# dcdr_3_2.net
KiCad netlist of a schematic drawn in EAGLE
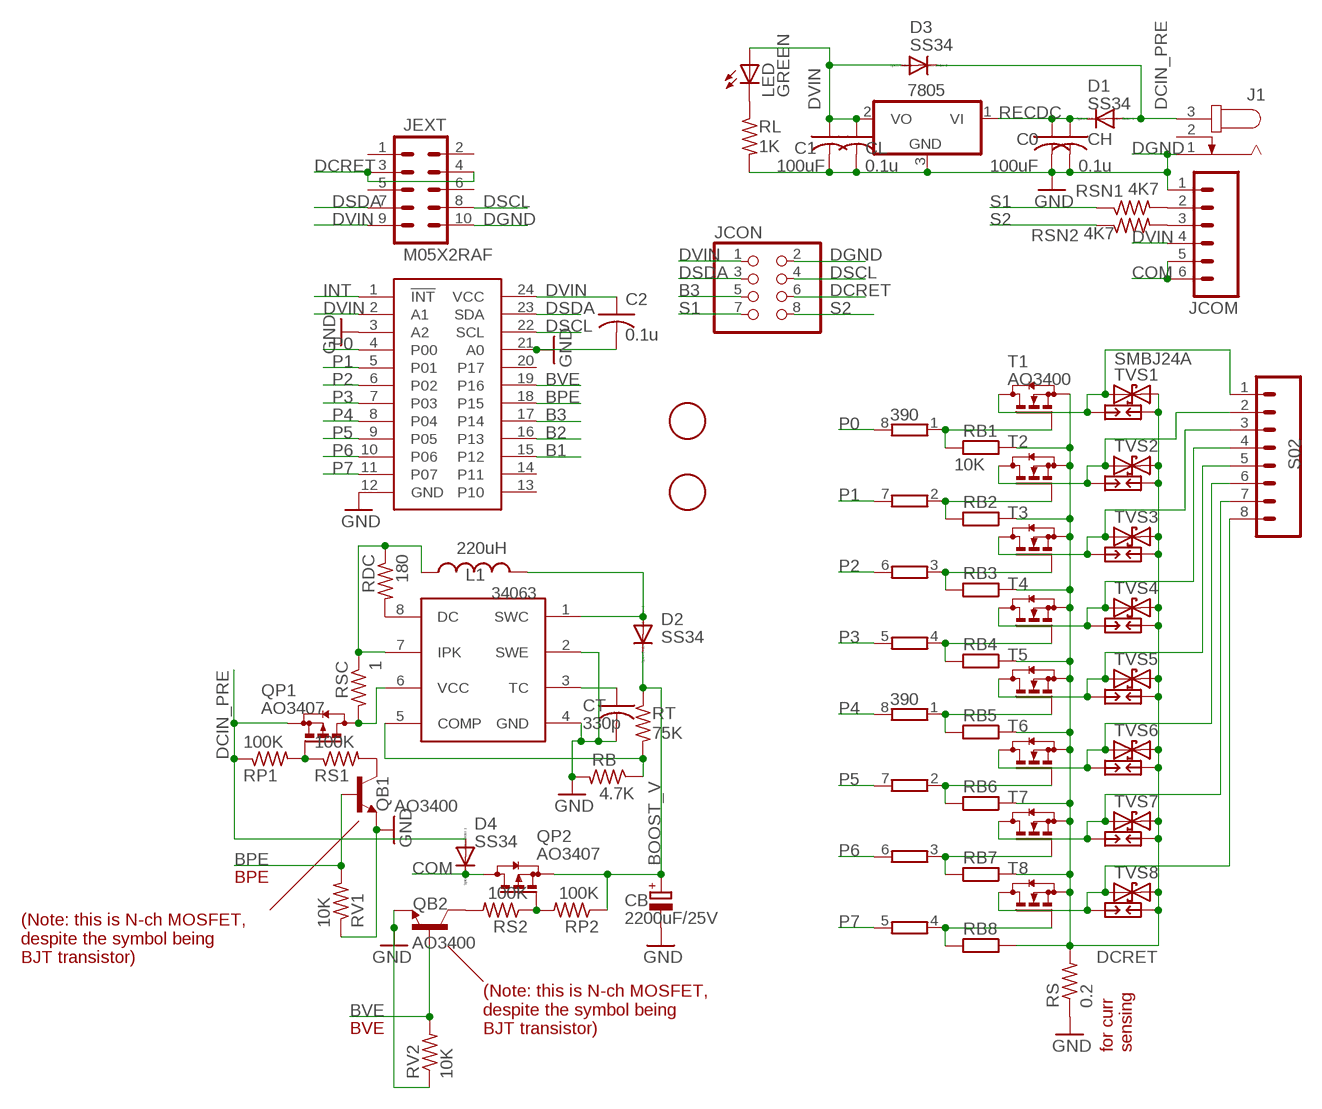
[diagram p0: schematic, sheet 1]

(export (version "E")
  (design (tool "Eeschema 10.0.6"))
  (components
    (comp (ref "7805")
      (value "7805DT")
      (footprint "eagle-import:TO252")
      (libsource (lib "eagle-import") (part "78DT05"))
    )
    (comp (ref "34063")
      (value "MC34063")
      (footprint "eagle-import:SO08")
      (libsource (lib "eagle-import") (part "MC33063/MC34063D"))
    )
    (comp (ref "C0")
      (value "100uF")
      (footprint "eagle-import:C0805K")
      (libsource (lib "eagle-import") (part "C-USC0805K"))
    )
    (comp (ref "C1")
      (value "100uF")
      (footprint "eagle-import:C0805K")
      (libsource (lib "eagle-import") (part "C-USC0805K"))
    )
    (comp (ref "C2")
      (value "0.1u")
      (footprint "eagle-import:C0603")
      (libsource (lib "eagle-import") (part "C-USC0603"))
    )
    (comp (ref "CB")
      (value "2200uF/25V")
      (footprint "eagle-import:E7,5-16")
      (libsource (lib "eagle-import") (part "CPOL-EUE7.5-16"))
    )
    (comp (ref "CH")
      (value "0.1u")
      (footprint "eagle-import:C0603")
      (libsource (lib "eagle-import") (part "C-USC0603"))
    )
    (comp (ref "CL")
      (value "0.1u")
      (footprint "eagle-import:C0603")
      (libsource (lib "eagle-import") (part "C-USC0603"))
    )
    (comp (ref "CT")
      (value "330p")
      (footprint "eagle-import:C0603K")
      (libsource (lib "eagle-import") (part "C-USC0603K"))
    )
    (comp (ref "D1")
      (value "SS34")
      (footprint "eagle-import:SMB")
      (libsource (lib "eagle-import") (part "DIODE-SMB"))
    )
    (comp (ref "D2")
      (value "SS34")
      (footprint "eagle-import:SMB")
      (libsource (lib "eagle-import") (part "DIODE-SMB"))
    )
    (comp (ref "D3")
      (value "SS34")
      (footprint "eagle-import:SMB")
      (libsource (lib "eagle-import") (part "DIODE-SMB"))
    )
    (comp (ref "D4")
      (value "SS34")
      (footprint "eagle-import:SMB")
      (libsource (lib "eagle-import") (part "DIODE-SMB"))
    )
    (comp (ref "J1")
      (value "JACK-PLUG0")
      (footprint "eagle-import:SPC4077")
      (libsource (lib "eagle-import") (part "JACK-PLUG0"))
    )
    (comp (ref "JCOM")
      (value "M065MM")
      (footprint "eagle-import:SCREWTERMINAL-5MM-6")
      (libsource (lib "eagle-import") (part "M065MM"))
    )
    (comp (ref "JCON")
      (value "PINHD-2X4")
      (footprint "eagle-import:2X04")
      (libsource (lib "eagle-import") (part "PINHD-2X4"))
    )
    (comp (ref "JEXT")
      (value "M05X2RAF")
      (footprint "eagle-import:2X5-RAF")
      (libsource (lib "eagle-import") (part "M05X2RAF"))
    )
    (comp (ref "L1")
      (value "220uH")
      (footprint "eagle-import:CR54")
      (libsource (lib "eagle-import") (part "INDUCTORCR54"))
    )
    (comp (ref "LED")
      (value "GREEN")
      (footprint "eagle-import:CHIPLED_0805")
      (libsource (lib "eagle-import") (part "LEDCHIPLED_0805"))
    )
    (comp (ref "PCA9555")
      (value "PCA9555")
      (footprint "eagle-import:TSSOP24")
      (libsource (lib "eagle-import") (part "PCF8575TSSOP24"))
    )
    (comp (ref "QB1")
      (value "AO3400")
      (footprint "eagle-import:SOT23-3")
      (libsource (lib "eagle-import") (part "TRANSISTOR_NPNSOT23-3"))
    )
    (comp (ref "QB2")
      (value "AO3400")
      (footprint "eagle-import:SOT23-3")
      (libsource (lib "eagle-import") (part "TRANSISTOR_NPNSOT23-3"))
    )
    (comp (ref "QP1")
      (value "AO3407")
      (footprint "eagle-import:SOT23")
      (libsource (lib "eagle-import") (part "BSS84"))
    )
    (comp (ref "QP2")
      (value "AO3407")
      (footprint "eagle-import:SOT23")
      (libsource (lib "eagle-import") (part "BSS84"))
    )
    (comp (ref "RB")
      (value "4.7K")
      (footprint "eagle-import:R0603")
      (libsource (lib "eagle-import") (part "adafruitGood_R-US_R0603"))
    )
    (comp (ref "RB1")
      (value "10K")
      (footprint "eagle-import:R0603")
      (libsource (lib "eagle-import") (part "R-EU_R0603"))
    )
    (comp (ref "RB2")
      (value "10K")
      (footprint "eagle-import:R0603")
      (libsource (lib "eagle-import") (part "R-EU_R0603"))
    )
    (comp (ref "RB3")
      (value "10K")
      (footprint "eagle-import:R0603")
      (libsource (lib "eagle-import") (part "R-EU_R0603"))
    )
    (comp (ref "RB4")
      (value "10K")
      (footprint "eagle-import:R0603")
      (libsource (lib "eagle-import") (part "R-EU_R0603"))
    )
    (comp (ref "RB5")
      (value "10K")
      (footprint "eagle-import:R0603")
      (libsource (lib "eagle-import") (part "R-EU_R0603"))
    )
    (comp (ref "RB6")
      (value "10K")
      (footprint "eagle-import:R0603")
      (libsource (lib "eagle-import") (part "R-EU_R0603"))
    )
    (comp (ref "RB7")
      (value "10K")
      (footprint "eagle-import:R0603")
      (libsource (lib "eagle-import") (part "R-EU_R0603"))
    )
    (comp (ref "RB8")
      (value "10K")
      (footprint "eagle-import:R0603")
      (libsource (lib "eagle-import") (part "R-EU_R0603"))
    )
    (comp (ref "RDC")
      (value "180")
      (footprint "eagle-import:R0603")
      (libsource (lib "eagle-import") (part "adafruitGood_R-US_R0603"))
    )
    (comp (ref "RL")
      (value "1K")
      (footprint "eagle-import:R0603")
      (libsource (lib "eagle-import") (part "adafruit2013_R-US_R0603"))
    )
    (comp (ref "RN1")
      (value "390")
      (footprint "eagle-import:EXB38V")
      (libsource (lib "eagle-import") (part "4R-NEXB38V"))
    )
    (comp (ref "RN2")
      (value "390")
      (footprint "eagle-import:EXB38V")
      (libsource (lib "eagle-import") (part "4R-NEXB38V"))
    )
    (comp (ref "RP1")
      (value "100K")
      (footprint "eagle-import:R0603")
      (libsource (lib "eagle-import") (part "adafruitGood_R-US_R0603"))
    )
    (comp (ref "RP2")
      (value "100K")
      (footprint "eagle-import:R0603")
      (libsource (lib "eagle-import") (part "adafruitGood_R-US_R0603"))
    )
    (comp (ref "RS")
      (value "0.2")
      (footprint "eagle-import:R2512")
      (libsource (lib "eagle-import") (part "R-US_R2512"))
    )
    (comp (ref "RS1")
      (value "100K")
      (footprint "eagle-import:R0603")
      (libsource (lib "eagle-import") (part "adafruitGood_R-US_R0603"))
    )
    (comp (ref "RS2")
      (value "100K")
      (footprint "eagle-import:R0603")
      (libsource (lib "eagle-import") (part "adafruitGood_R-US_R0603"))
    )
    (comp (ref "RSC")
      (value "1")
      (footprint "eagle-import:R0603")
      (libsource (lib "eagle-import") (part "adafruitGood_R-US_R0603"))
    )
    (comp (ref "RSN1")
      (value "4K7")
      (footprint "eagle-import:R0603")
      (libsource (lib "eagle-import") (part "adafruit2013_R-US_R0603"))
    )
    (comp (ref "RSN2")
      (value "4K7")
      (footprint "eagle-import:R0603")
      (libsource (lib "eagle-import") (part "adafruit2013_R-US_R0603"))
    )
    (comp (ref "RT")
      (value "75K")
      (footprint "eagle-import:R0603")
      (libsource (lib "eagle-import") (part "adafruitGood_R-US_R0603"))
    )
    (comp (ref "RV1")
      (value "10K")
      (footprint "eagle-import:R0603")
      (libsource (lib "eagle-import") (part "adafruitGood_R-US_R0603"))
    )
    (comp (ref "RV2")
      (value "10K")
      (footprint "eagle-import:R0603")
      (libsource (lib "eagle-import") (part "adafruitGood_R-US_R0603"))
    )
    (comp (ref "S02")
      (value "M085MM-8")
      (footprint "eagle-import:SCREWTERMINAL-5MM-8")
      (libsource (lib "eagle-import") (part "M085MM-8"))
    )
    (comp (ref "SP1")
      (value "PCB-SGAP")
      (footprint "eagle-import:PCB-SGAP")
      (libsource (lib "eagle-import") (part "PCB-SGAP"))
    )
    (comp (ref "SP2")
      (value "PCB-SGAP")
      (footprint "eagle-import:PCB-SGAP")
      (libsource (lib "eagle-import") (part "PCB-SGAP"))
    )
    (comp (ref "SP3")
      (value "PCB-SGAP")
      (footprint "eagle-import:PCB-SGAP")
      (libsource (lib "eagle-import") (part "PCB-SGAP"))
    )
    (comp (ref "SP4")
      (value "PCB-SGAP")
      (footprint "eagle-import:PCB-SGAP")
      (libsource (lib "eagle-import") (part "PCB-SGAP"))
    )
    (comp (ref "SP5")
      (value "PCB-SGAP")
      (footprint "eagle-import:PCB-SGAP")
      (libsource (lib "eagle-import") (part "PCB-SGAP"))
    )
    (comp (ref "SP6")
      (value "PCB-SGAP")
      (footprint "eagle-import:PCB-SGAP")
      (libsource (lib "eagle-import") (part "PCB-SGAP"))
    )
    (comp (ref "SP7")
      (value "PCB-SGAP")
      (footprint "eagle-import:PCB-SGAP")
      (libsource (lib "eagle-import") (part "PCB-SGAP"))
    )
    (comp (ref "SP8")
      (value "PCB-SGAP")
      (footprint "eagle-import:PCB-SGAP")
      (libsource (lib "eagle-import") (part "PCB-SGAP"))
    )
    (comp (ref "T1")
      (value "AO3400")
      (footprint "eagle-import:SOT23")
      (libsource (lib "eagle-import") (part "BSS123"))
    )
    (comp (ref "T2")
      (value "AO3400")
      (footprint "eagle-import:SOT23")
      (libsource (lib "eagle-import") (part "BSS123"))
    )
    (comp (ref "T3")
      (value "AO3400")
      (footprint "eagle-import:SOT23")
      (libsource (lib "eagle-import") (part "BSS123"))
    )
    (comp (ref "T4")
      (value "AO3400")
      (footprint "eagle-import:SOT23")
      (libsource (lib "eagle-import") (part "BSS123"))
    )
    (comp (ref "T5")
      (value "AO3400")
      (footprint "eagle-import:SOT23")
      (libsource (lib "eagle-import") (part "BSS123"))
    )
    (comp (ref "T6")
      (value "AO3400")
      (footprint "eagle-import:SOT23")
      (libsource (lib "eagle-import") (part "BSS123"))
    )
    (comp (ref "T7")
      (value "AO3400")
      (footprint "eagle-import:SOT23")
      (libsource (lib "eagle-import") (part "BSS123"))
    )
    (comp (ref "T8")
      (value "AO3400")
      (footprint "eagle-import:SOT23")
      (libsource (lib "eagle-import") (part "BSS123"))
    )
    (comp (ref "TVS1")
      (value "SMBJ24A")
      (footprint "eagle-import:SMB")
      (libsource (lib "eagle-import") (part "TVSSMB"))
    )
    (comp (ref "TVS2")
      (value "SMBJ24A")
      (footprint "eagle-import:SMB")
      (libsource (lib "eagle-import") (part "TVSSMB"))
    )
    (comp (ref "TVS3")
      (value "SMBJ24A")
      (footprint "eagle-import:SMB")
      (libsource (lib "eagle-import") (part "TVSSMB"))
    )
    (comp (ref "TVS4")
      (value "SMBJ24A")
      (footprint "eagle-import:SMB")
      (libsource (lib "eagle-import") (part "TVSSMB"))
    )
    (comp (ref "TVS5")
      (value "SMBJ24A")
      (footprint "eagle-import:SMB")
      (libsource (lib "eagle-import") (part "TVSSMB"))
    )
    (comp (ref "TVS6")
      (value "SMBJ24A")
      (footprint "eagle-import:SMB")
      (libsource (lib "eagle-import") (part "TVSSMB"))
    )
    (comp (ref "TVS7")
      (value "SMBJ24A")
      (footprint "eagle-import:SMB")
      (libsource (lib "eagle-import") (part "TVSSMB"))
    )
    (comp (ref "TVS8")
      (value "SMBJ24A")
      (footprint "eagle-import:SMB")
      (libsource (lib "eagle-import") (part "TVSSMB"))
    )
    (comp (ref "U$1")
      (value "FIDUCIAL")
      (footprint "eagle-import:FIDUCIAL_1MM")
      (libsource (lib "eagle-import") (part "FIDUCIAL"))
    )
    (comp (ref "U$2")
      (value "FIDUCIAL")
      (footprint "eagle-import:FIDUCIAL_1MM")
      (libsource (lib "eagle-import") (part "FIDUCIAL"))
    )
  )
  (nets
    (net (code "1") (name "/B1") (class "Default")
      (node (ref "PCA9555") (pin "15") (pinfunction "P12_15") (pintype "bidirectional"))
    )
    (net (code "2") (name "/B2") (class "Default")
      (node (ref "PCA9555") (pin "16") (pinfunction "P13_16") (pintype "bidirectional"))
    )
    (net (code "3") (name "/B3") (class "Default")
      (node (ref "JCON") (pin "5") (pinfunction "5_5") (pintype "passive"))
      (node (ref "PCA9555") (pin "17") (pinfunction "P14_17") (pintype "bidirectional"))
    )
    (net (code "4") (name "/BOOST_V") (class "Default")
      (node (ref "CB") (pin "+") (pinfunction "+_+") (pintype "passive"))
      (node (ref "D2") (pin "C") (pinfunction "C_C") (pintype "passive"))
      (node (ref "QP2") (pin "2") (pinfunction "S_2") (pintype "passive"))
      (node (ref "RP2") (pin "1") (pinfunction "1_1") (pintype "passive"))
      (node (ref "RT") (pin "1") (pinfunction "1_1") (pintype "passive"))
    )
    (net (code "5") (name "/BPE") (class "Default")
      (node (ref "PCA9555") (pin "18") (pinfunction "P15_18") (pintype "bidirectional"))
      (node (ref "QB1") (pin "1") (pinfunction "B_1") (pintype "passive"))
      (node (ref "RV1") (pin "2") (pinfunction "2_2") (pintype "passive"))
    )
    (net (code "6") (name "/BVE") (class "Default")
      (node (ref "PCA9555") (pin "19") (pinfunction "P16_19") (pintype "bidirectional"))
      (node (ref "QB2") (pin "1") (pinfunction "B_1") (pintype "passive"))
      (node (ref "RV2") (pin "2") (pinfunction "2_2") (pintype "passive"))
    )
    (net (code "7") (name "/COM") (class "Default")
      (node (ref "D4") (pin "C") (pinfunction "C_C") (pintype "passive"))
      (node (ref "JCOM") (pin "5") (pinfunction "5_5") (pintype "passive"))
      (node (ref "JCOM") (pin "6") (pinfunction "6_6") (pintype "passive"))
      (node (ref "QP2") (pin "3") (pinfunction "D_3") (pintype "passive"))
    )
    (net (code "8") (name "/DCIN_PRE") (class "Default")
      (node (ref "D1") (pin "A") (pinfunction "A_A") (pintype "passive"))
      (node (ref "D3") (pin "C") (pinfunction "C_C") (pintype "passive"))
      (node (ref "D4") (pin "A") (pinfunction "A_A") (pintype "passive"))
      (node (ref "J1") (pin "3") (pinfunction "3_3") (pintype "passive"))
      (node (ref "QP1") (pin "2") (pinfunction "S_2") (pintype "passive"))
      (node (ref "RP1") (pin "1") (pinfunction "1_1") (pintype "passive"))
    )
    (net (code "9") (name "/DCRET") (class "Default")
      (node (ref "JCON") (pin "6") (pinfunction "6_6") (pintype "passive"))
      (node (ref "JEXT") (pin "3") (pinfunction "3_3") (pintype "passive"))
      (node (ref "JEXT") (pin "4") (pinfunction "4_4") (pintype "passive"))
      (node (ref "RB1") (pin "1") (pinfunction "1_1") (pintype "passive"))
      (node (ref "RB2") (pin "1") (pinfunction "1_1") (pintype "passive"))
      (node (ref "RB3") (pin "1") (pinfunction "1_1") (pintype "passive"))
      (node (ref "RB4") (pin "1") (pinfunction "1_1") (pintype "passive"))
      (node (ref "RB5") (pin "1") (pinfunction "1_1") (pintype "passive"))
      (node (ref "RB6") (pin "1") (pinfunction "1_1") (pintype "passive"))
      (node (ref "RB7") (pin "1") (pinfunction "1_1") (pintype "passive"))
      (node (ref "RB8") (pin "1") (pinfunction "1_1") (pintype "passive"))
      (node (ref "RS") (pin "2") (pinfunction "2_2") (pintype "passive"))
      (node (ref "SP1") (pin "1") (pinfunction "1_1") (pintype "passive"))
      (node (ref "SP2") (pin "1") (pinfunction "1_1") (pintype "passive"))
      (node (ref "SP3") (pin "1") (pinfunction "1_1") (pintype "passive"))
      (node (ref "SP4") (pin "1") (pinfunction "1_1") (pintype "passive"))
      (node (ref "SP5") (pin "1") (pinfunction "1_1") (pintype "passive"))
      (node (ref "SP6") (pin "1") (pinfunction "1_1") (pintype "passive"))
      (node (ref "SP7") (pin "1") (pinfunction "1_1") (pintype "passive"))
      (node (ref "SP8") (pin "1") (pinfunction "1_1") (pintype "passive"))
      (node (ref "T1") (pin "2") (pinfunction "S_2") (pintype "passive"))
      (node (ref "T2") (pin "2") (pinfunction "S_2") (pintype "passive"))
      (node (ref "T3") (pin "2") (pinfunction "S_2") (pintype "passive"))
      (node (ref "T4") (pin "2") (pinfunction "S_2") (pintype "passive"))
      (node (ref "T5") (pin "2") (pinfunction "S_2") (pintype "passive"))
      (node (ref "T6") (pin "2") (pinfunction "S_2") (pintype "passive"))
      (node (ref "T7") (pin "2") (pinfunction "S_2") (pintype "passive"))
      (node (ref "T8") (pin "2") (pinfunction "S_2") (pintype "passive"))
      (node (ref "TVS1") (pin "C") (pinfunction "C_C") (pintype "passive"))
      (node (ref "TVS2") (pin "C") (pinfunction "C_C") (pintype "passive"))
      (node (ref "TVS3") (pin "C") (pinfunction "C_C") (pintype "passive"))
      (node (ref "TVS4") (pin "C") (pinfunction "C_C") (pintype "passive"))
      (node (ref "TVS5") (pin "C") (pinfunction "C_C") (pintype "passive"))
      (node (ref "TVS6") (pin "C") (pinfunction "C_C") (pintype "passive"))
      (node (ref "TVS7") (pin "C") (pinfunction "C_C") (pintype "passive"))
      (node (ref "TVS8") (pin "C") (pinfunction "C_C") (pintype "passive"))
    )
    (net (code "10") (name "/DSCL") (class "Default")
      (node (ref "JCON") (pin "4") (pinfunction "4_4") (pintype "passive"))
      (node (ref "JEXT") (pin "8") (pinfunction "8_8") (pintype "passive"))
      (node (ref "PCA9555") (pin "22") (pinfunction "SCL_22") (pintype "bidirectional"))
    )
    (net (code "11") (name "/DSDA") (class "Default")
      (node (ref "JCON") (pin "3") (pinfunction "3_3") (pintype "passive"))
      (node (ref "JEXT") (pin "7") (pinfunction "7_7") (pintype "passive"))
      (node (ref "PCA9555") (pin "23") (pinfunction "SDA_23") (pintype "bidirectional"))
    )
    (net (code "12") (name "/DVIN") (class "Default")
      (node (ref "7805") (pin "2") (pinfunction "VO_2") (pintype "passive"))
      (node (ref "C1") (pin "1") (pinfunction "1_1") (pintype "passive"))
      (node (ref "C2") (pin "1") (pinfunction "1_1") (pintype "passive"))
      (node (ref "CL") (pin "1") (pinfunction "1_1") (pintype "passive"))
      (node (ref "D3") (pin "A") (pinfunction "A_A") (pintype "passive"))
      (node (ref "JCOM") (pin "4") (pinfunction "4_4") (pintype "passive"))
      (node (ref "JCON") (pin "1") (pinfunction "1_1") (pintype "passive"))
      (node (ref "JEXT") (pin "9") (pinfunction "9_9") (pintype "passive"))
      (node (ref "LED") (pin "A") (pinfunction "A_A") (pintype "passive"))
      (node (ref "PCA9555") (pin "2") (pinfunction "A1_2") (pintype "bidirectional"))
      (node (ref "PCA9555") (pin "24") (pinfunction "VCC_24") (pintype "power_in"))
    )
    (net (code "13") (name "/INT") (class "Default")
      (node (ref "PCA9555") (pin "1") (pinfunction "~{INT}_1") (pintype "bidirectional"))
    )
    (net (code "14") (name "/P0") (class "Default")
      (node (ref "PCA9555") (pin "4") (pinfunction "P00_4") (pintype "bidirectional"))
      (node (ref "RN1") (pin "8") (pinfunction "2_8") (pintype "passive"))
    )
    (net (code "15") (name "/P1") (class "Default")
      (node (ref "PCA9555") (pin "5") (pinfunction "P01_5") (pintype "bidirectional"))
      (node (ref "RN1") (pin "7") (pinfunction "2_7") (pintype "passive"))
    )
    (net (code "16") (name "/P2") (class "Default")
      (node (ref "PCA9555") (pin "6") (pinfunction "P02_6") (pintype "bidirectional"))
      (node (ref "RN1") (pin "6") (pinfunction "2_6") (pintype "passive"))
    )
    (net (code "17") (name "/P3") (class "Default")
      (node (ref "PCA9555") (pin "7") (pinfunction "P03_7") (pintype "bidirectional"))
      (node (ref "RN1") (pin "5") (pinfunction "2_5") (pintype "passive"))
    )
    (net (code "18") (name "/P4") (class "Default")
      (node (ref "PCA9555") (pin "8") (pinfunction "P04_8") (pintype "bidirectional"))
      (node (ref "RN2") (pin "8") (pinfunction "2_8") (pintype "passive"))
    )
    (net (code "19") (name "/P5") (class "Default")
      (node (ref "PCA9555") (pin "9") (pinfunction "P05_9") (pintype "bidirectional"))
      (node (ref "RN2") (pin "7") (pinfunction "2_7") (pintype "passive"))
    )
    (net (code "20") (name "/P6") (class "Default")
      (node (ref "PCA9555") (pin "10") (pinfunction "P06_10") (pintype "bidirectional"))
      (node (ref "RN2") (pin "6") (pinfunction "2_6") (pintype "passive"))
    )
    (net (code "21") (name "/P7") (class "Default")
      (node (ref "PCA9555") (pin "11") (pinfunction "P07_11") (pintype "bidirectional"))
      (node (ref "RN2") (pin "5") (pinfunction "2_5") (pintype "passive"))
    )
    (net (code "22") (name "/RECDC") (class "Default")
      (node (ref "7805") (pin "1") (pinfunction "VI_1") (pintype "input"))
      (node (ref "C0") (pin "1") (pinfunction "1_1") (pintype "passive"))
      (node (ref "CH") (pin "1") (pinfunction "1_1") (pintype "passive"))
      (node (ref "D1") (pin "C") (pinfunction "C_C") (pintype "passive"))
    )
    (net (code "23") (name "/S1") (class "Default")
      (node (ref "JCON") (pin "7") (pinfunction "7_7") (pintype "passive"))
      (node (ref "RSN1") (pin "1") (pinfunction "1_1") (pintype "passive"))
    )
    (net (code "24") (name "/S2") (class "Default")
      (node (ref "JCON") (pin "8") (pinfunction "8_8") (pintype "passive"))
      (node (ref "RSN2") (pin "1") (pinfunction "1_1") (pintype "passive"))
    )
    (net (code "25") (name "GND") (class "Default")
      (node (ref "34063") (pin "2") (pinfunction "SWE_2") (pintype "input"))
      (node (ref "34063") (pin "4") (pinfunction "GND_4") (pintype "power_in"))
      (node (ref "7805") (pin "3") (pinfunction "GND_3") (pintype "passive"))
      (node (ref "C0") (pin "2") (pinfunction "2_2") (pintype "passive"))
      (node (ref "C1") (pin "2") (pinfunction "2_2") (pintype "passive"))
      (node (ref "C2") (pin "2") (pinfunction "2_2") (pintype "passive"))
      (node (ref "CB") (pin "-") (pinfunction "-_-") (pintype "passive"))
      (node (ref "CH") (pin "2") (pinfunction "2_2") (pintype "passive"))
      (node (ref "CL") (pin "2") (pinfunction "2_2") (pintype "passive"))
      (node (ref "CT") (pin "2") (pinfunction "2_2") (pintype "passive"))
      (node (ref "J1") (pin "1") (pinfunction "1_1") (pintype "passive"))
      (node (ref "JCOM") (pin "1") (pinfunction "1_1") (pintype "passive"))
      (node (ref "JCON") (pin "2") (pinfunction "2_2") (pintype "passive"))
      (node (ref "JEXT") (pin "10") (pinfunction "10_10") (pintype "passive"))
      (node (ref "PCA9555") (pin "12") (pinfunction "GND_12") (pintype "power_in"))
      (node (ref "PCA9555") (pin "21") (pinfunction "A0_21") (pintype "bidirectional"))
      (node (ref "PCA9555") (pin "3") (pinfunction "A2_3") (pintype "bidirectional"))
      (node (ref "QB1") (pin "2") (pinfunction "E_2") (pintype "passive"))
      (node (ref "QB2") (pin "2") (pinfunction "E_2") (pintype "passive"))
      (node (ref "RB") (pin "2") (pinfunction "2_2") (pintype "passive"))
      (node (ref "RL") (pin "2") (pinfunction "2_2") (pintype "passive"))
      (node (ref "RS") (pin "1") (pinfunction "1_1") (pintype "passive"))
      (node (ref "RV1") (pin "1") (pinfunction "1_1") (pintype "passive"))
      (node (ref "RV2") (pin "1") (pinfunction "1_1") (pintype "passive"))
    )
    (net (code "26") (name "Net-(34063-COMP)") (class "Default")
      (node (ref "34063") (pin "5") (pinfunction "COMP_5") (pintype "input"))
      (node (ref "RB") (pin "1") (pinfunction "1_1") (pintype "passive"))
      (node (ref "RT") (pin "2") (pinfunction "2_2") (pintype "passive"))
    )
    (net (code "27") (name "Net-(34063-DC)") (class "Default")
      (node (ref "34063") (pin "8") (pinfunction "DC_8") (pintype "input"))
      (node (ref "RDC") (pin "2") (pinfunction "2_2") (pintype "passive"))
    )
    (net (code "28") (name "Net-(34063-IPK)") (class "Default")
      (node (ref "34063") (pin "7") (pinfunction "IPK_7") (pintype "bidirectional"))
      (node (ref "L1") (pin "P$1") (pinfunction "1_P$1") (pintype "passive"))
      (node (ref "RDC") (pin "1") (pinfunction "1_1") (pintype "passive"))
      (node (ref "RSC") (pin "1") (pinfunction "1_1") (pintype "passive"))
    )
    (net (code "29") (name "Net-(34063-SWC)") (class "Default")
      (node (ref "34063") (pin "1") (pinfunction "SWC_1") (pintype "input"))
      (node (ref "D2") (pin "A") (pinfunction "A_A") (pintype "passive"))
      (node (ref "L1") (pin "P$2") (pinfunction "2_P$2") (pintype "passive"))
    )
    (net (code "30") (name "Net-(34063-TC)") (class "Default")
      (node (ref "34063") (pin "3") (pinfunction "TC_3") (pintype "input"))
      (node (ref "CT") (pin "1") (pinfunction "1_1") (pintype "passive"))
    )
    (net (code "31") (name "Net-(34063-VCC)") (class "Default")
      (node (ref "34063") (pin "6") (pinfunction "VCC_6") (pintype "power_in"))
      (node (ref "QP1") (pin "3") (pinfunction "D_3") (pintype "passive"))
      (node (ref "RSC") (pin "2") (pinfunction "2_2") (pintype "passive"))
    )
    (net (code "32") (name "Net-(JCOM-Pad2)") (class "Default")
      (node (ref "JCOM") (pin "2") (pinfunction "2_2") (pintype "passive"))
      (node (ref "RSN1") (pin "2") (pinfunction "2_2") (pintype "passive"))
    )
    (net (code "33") (name "Net-(JCOM-Pad3)") (class "Default")
      (node (ref "JCOM") (pin "3") (pinfunction "3_3") (pintype "passive"))
      (node (ref "RSN2") (pin "2") (pinfunction "2_2") (pintype "passive"))
    )
    (net (code "34") (name "Net-(LED-PadC)") (class "Default")
      (node (ref "LED") (pin "C") (pinfunction "C_C") (pintype "passive"))
      (node (ref "RL") (pin "1") (pinfunction "1_1") (pintype "passive"))
    )
    (net (code "35") (name "Net-(QB1-C)") (class "Default")
      (node (ref "QB1") (pin "3") (pinfunction "C_3") (pintype "passive"))
      (node (ref "RS1") (pin "2") (pinfunction "2_2") (pintype "passive"))
    )
    (net (code "36") (name "Net-(QB2-C)") (class "Default")
      (node (ref "QB2") (pin "3") (pinfunction "C_3") (pintype "passive"))
      (node (ref "RS2") (pin "2") (pinfunction "2_2") (pintype "passive"))
    )
    (net (code "37") (name "Net-(QP1-G)") (class "Default")
      (node (ref "QP1") (pin "1") (pinfunction "G_1") (pintype "passive"))
      (node (ref "RP1") (pin "2") (pinfunction "2_2") (pintype "passive"))
      (node (ref "RS1") (pin "1") (pinfunction "1_1") (pintype "passive"))
    )
    (net (code "38") (name "Net-(QP2-G)") (class "Default")
      (node (ref "QP2") (pin "1") (pinfunction "G_1") (pintype "passive"))
      (node (ref "RP2") (pin "2") (pinfunction "2_2") (pintype "passive"))
      (node (ref "RS2") (pin "1") (pinfunction "1_1") (pintype "passive"))
    )
    (net (code "39") (name "Net-(RN1B-1)") (class "Default")
      (node (ref "RB2") (pin "2") (pinfunction "2_2") (pintype "passive"))
      (node (ref "RN1") (pin "2") (pinfunction "1_2") (pintype "passive"))
      (node (ref "T2") (pin "1") (pinfunction "G_1") (pintype "passive"))
    )
    (net (code "40") (name "Net-(RN1C-1)") (class "Default")
      (node (ref "RB3") (pin "2") (pinfunction "2_2") (pintype "passive"))
      (node (ref "RN1") (pin "3") (pinfunction "1_3") (pintype "passive"))
      (node (ref "T3") (pin "1") (pinfunction "G_1") (pintype "passive"))
    )
    (net (code "41") (name "Net-(RN1D-1)") (class "Default")
      (node (ref "RB4") (pin "2") (pinfunction "2_2") (pintype "passive"))
      (node (ref "RN1") (pin "4") (pinfunction "1_4") (pintype "passive"))
      (node (ref "T4") (pin "1") (pinfunction "G_1") (pintype "passive"))
    )
    (net (code "42") (name "Net-(RN2B-1)") (class "Default")
      (node (ref "RB6") (pin "2") (pinfunction "2_2") (pintype "passive"))
      (node (ref "RN2") (pin "2") (pinfunction "1_2") (pintype "passive"))
      (node (ref "T6") (pin "1") (pinfunction "G_1") (pintype "passive"))
    )
    (net (code "43") (name "Net-(RN2C-1)") (class "Default")
      (node (ref "RB7") (pin "2") (pinfunction "2_2") (pintype "passive"))
      (node (ref "RN2") (pin "3") (pinfunction "1_3") (pintype "passive"))
      (node (ref "T7") (pin "1") (pinfunction "G_1") (pintype "passive"))
    )
    (net (code "44") (name "Net-(RN2D-1)") (class "Default")
      (node (ref "RB8") (pin "2") (pinfunction "2_2") (pintype "passive"))
      (node (ref "RN2") (pin "4") (pinfunction "1_4") (pintype "passive"))
      (node (ref "T8") (pin "1") (pinfunction "G_1") (pintype "passive"))
    )
    (net (code "45") (name "Net-(T1-D)") (class "Default")
      (node (ref "S02") (pin "1") (pinfunction "1_1") (pintype "passive"))
      (node (ref "SP1") (pin "2") (pinfunction "2_2") (pintype "passive"))
      (node (ref "T1") (pin "3") (pinfunction "D_3") (pintype "passive"))
      (node (ref "TVS1") (pin "A") (pinfunction "A_A") (pintype "passive"))
    )
    (net (code "46") (name "Net-(T1-G)") (class "Default")
      (node (ref "RB1") (pin "2") (pinfunction "2_2") (pintype "passive"))
      (node (ref "RN1") (pin "1") (pinfunction "1_1") (pintype "passive"))
      (node (ref "T1") (pin "1") (pinfunction "G_1") (pintype "passive"))
    )
    (net (code "47") (name "Net-(T2-D)") (class "Default")
      (node (ref "S02") (pin "2") (pinfunction "2_2") (pintype "passive"))
      (node (ref "SP2") (pin "2") (pinfunction "2_2") (pintype "passive"))
      (node (ref "T2") (pin "3") (pinfunction "D_3") (pintype "passive"))
      (node (ref "TVS2") (pin "A") (pinfunction "A_A") (pintype "passive"))
    )
    (net (code "48") (name "Net-(T3-D)") (class "Default")
      (node (ref "S02") (pin "3") (pinfunction "3_3") (pintype "passive"))
      (node (ref "SP3") (pin "2") (pinfunction "2_2") (pintype "passive"))
      (node (ref "T3") (pin "3") (pinfunction "D_3") (pintype "passive"))
      (node (ref "TVS3") (pin "A") (pinfunction "A_A") (pintype "passive"))
    )
    (net (code "49") (name "Net-(T4-D)") (class "Default")
      (node (ref "S02") (pin "4") (pinfunction "4_4") (pintype "passive"))
      (node (ref "SP4") (pin "2") (pinfunction "2_2") (pintype "passive"))
      (node (ref "T4") (pin "3") (pinfunction "D_3") (pintype "passive"))
      (node (ref "TVS4") (pin "A") (pinfunction "A_A") (pintype "passive"))
    )
    (net (code "50") (name "Net-(T5-D)") (class "Default")
      (node (ref "S02") (pin "5") (pinfunction "5_5") (pintype "passive"))
      (node (ref "SP5") (pin "2") (pinfunction "2_2") (pintype "passive"))
      (node (ref "T5") (pin "3") (pinfunction "D_3") (pintype "passive"))
      (node (ref "TVS5") (pin "A") (pinfunction "A_A") (pintype "passive"))
    )
    (net (code "51") (name "Net-(T5-G)") (class "Default")
      (node (ref "RB5") (pin "2") (pinfunction "2_2") (pintype "passive"))
      (node (ref "RN2") (pin "1") (pinfunction "1_1") (pintype "passive"))
      (node (ref "T5") (pin "1") (pinfunction "G_1") (pintype "passive"))
    )
    (net (code "52") (name "Net-(T6-D)") (class "Default")
      (node (ref "S02") (pin "6") (pinfunction "6_6") (pintype "passive"))
      (node (ref "SP6") (pin "2") (pinfunction "2_2") (pintype "passive"))
      (node (ref "T6") (pin "3") (pinfunction "D_3") (pintype "passive"))
      (node (ref "TVS6") (pin "A") (pinfunction "A_A") (pintype "passive"))
    )
    (net (code "53") (name "Net-(T7-D)") (class "Default")
      (node (ref "S02") (pin "7") (pinfunction "7_7") (pintype "passive"))
      (node (ref "SP7") (pin "2") (pinfunction "2_2") (pintype "passive"))
      (node (ref "T7") (pin "3") (pinfunction "D_3") (pintype "passive"))
      (node (ref "TVS7") (pin "A") (pinfunction "A_A") (pintype "passive"))
    )
    (net (code "54") (name "Net-(T8-D)") (class "Default")
      (node (ref "S02") (pin "8") (pinfunction "8_8") (pintype "passive"))
      (node (ref "SP8") (pin "2") (pinfunction "2_2") (pintype "passive"))
      (node (ref "T8") (pin "3") (pinfunction "D_3") (pintype "passive"))
      (node (ref "TVS8") (pin "A") (pinfunction "A_A") (pintype "passive"))
    )
    (net (code "55") (name "unconnected-(J1-Pad2)") (class "Default")
      (node (ref "J1") (pin "2") (pinfunction "2_2") (pintype "passive"))
    )
    (net (code "56") (name "unconnected-(JEXT-Pad1)") (class "Default")
      (node (ref "JEXT") (pin "1") (pinfunction "1_1") (pintype "passive"))
    )
    (net (code "57") (name "unconnected-(JEXT-Pad2)") (class "Default")
      (node (ref "JEXT") (pin "2") (pinfunction "2_2") (pintype "passive"))
    )
    (net (code "58") (name "unconnected-(JEXT-Pad5)") (class "Default")
      (node (ref "JEXT") (pin "5") (pinfunction "5_5") (pintype "passive"))
    )
    (net (code "59") (name "unconnected-(JEXT-Pad6)") (class "Default")
      (node (ref "JEXT") (pin "6") (pinfunction "6_6") (pintype "passive"))
    )
    (net (code "60") (name "unconnected-(PCA9555-P10-Pad13)") (class "Default")
      (node (ref "PCA9555") (pin "13") (pinfunction "P10_13") (pintype "bidirectional"))
    )
    (net (code "61") (name "unconnected-(PCA9555-P11-Pad14)") (class "Default")
      (node (ref "PCA9555") (pin "14") (pinfunction "P11_14") (pintype "bidirectional"))
    )
    (net (code "62") (name "unconnected-(PCA9555-P17-Pad20)") (class "Default")
      (node (ref "PCA9555") (pin "20") (pinfunction "P17_20") (pintype "bidirectional"))
    )
  )
)
